# 4x4.net
KiCad netlist of a schematic drawn in Altium Designer
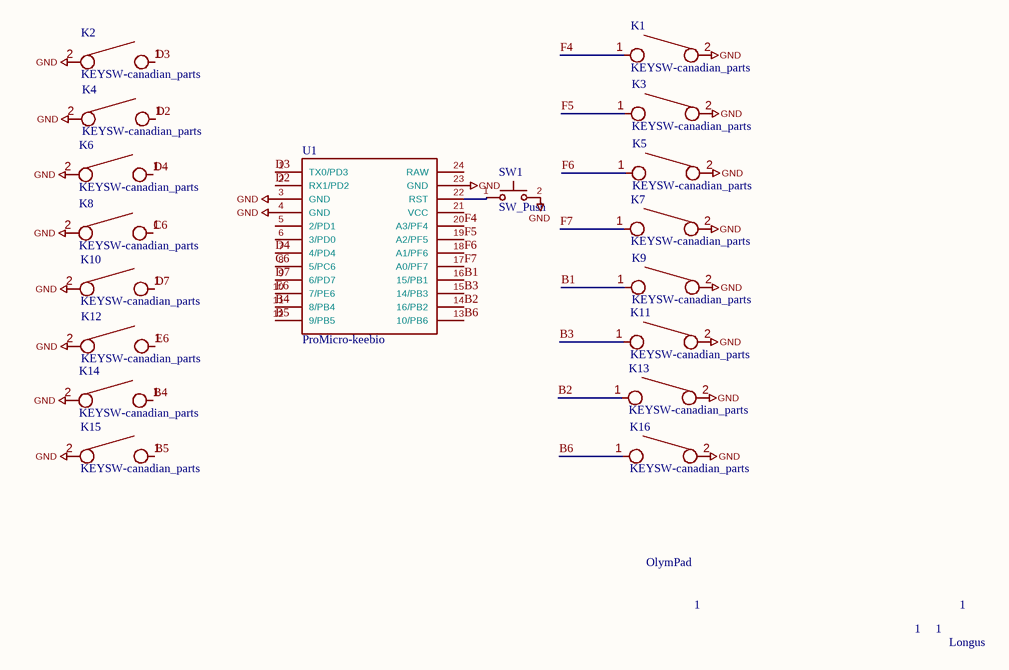
[diagram p0: 4x4.SchDoc]

(export (version "E")
  (design (tool "Eeschema 10.0.6"))
  (components
    (comp (ref "K1")
      (value "KEYSW-canadian_parts")
      (footprint "Socket")
      (libsource (lib "Macropad") (part "KEYSW-canadian_parts"))
    )
    (comp (ref "K2")
      (value "KEYSW-canadian_parts")
      (footprint "Socket")
      (libsource (lib "Macropad") (part "KEYSW-canadian_parts"))
    )
    (comp (ref "K3")
      (value "KEYSW-canadian_parts")
      (footprint "Socket")
      (libsource (lib "Macropad") (part "KEYSW-canadian_parts"))
    )
    (comp (ref "K4")
      (value "KEYSW-canadian_parts")
      (footprint "Socket")
      (libsource (lib "Macropad") (part "KEYSW-canadian_parts"))
    )
    (comp (ref "K5")
      (value "KEYSW-canadian_parts")
      (footprint "Socket")
      (libsource (lib "Macropad") (part "KEYSW-canadian_parts"))
    )
    (comp (ref "K6")
      (value "KEYSW-canadian_parts")
      (footprint "Socket")
      (libsource (lib "Macropad") (part "KEYSW-canadian_parts"))
    )
    (comp (ref "K7")
      (value "KEYSW-canadian_parts")
      (footprint "Socket")
      (libsource (lib "Macropad") (part "KEYSW-canadian_parts"))
    )
    (comp (ref "K8")
      (value "KEYSW-canadian_parts")
      (footprint "Socket")
      (libsource (lib "Macropad") (part "KEYSW-canadian_parts"))
    )
    (comp (ref "K9")
      (value "KEYSW-canadian_parts")
      (footprint "Socket")
      (libsource (lib "Macropad") (part "KEYSW-canadian_parts"))
    )
    (comp (ref "K10")
      (value "KEYSW-canadian_parts")
      (footprint "Socket")
      (libsource (lib "Macropad") (part "KEYSW-canadian_parts"))
    )
    (comp (ref "K11")
      (value "KEYSW-canadian_parts")
      (footprint "Socket")
      (libsource (lib "Macropad") (part "KEYSW-canadian_parts"))
    )
    (comp (ref "K12")
      (value "KEYSW-canadian_parts")
      (footprint "Socket")
      (libsource (lib "Macropad") (part "KEYSW-canadian_parts"))
    )
    (comp (ref "K13")
      (value "KEYSW-canadian_parts")
      (footprint "Socket")
      (libsource (lib "Macropad") (part "KEYSW-canadian_parts"))
    )
    (comp (ref "K14")
      (value "KEYSW-canadian_parts")
      (footprint "Socket")
      (libsource (lib "Macropad") (part "KEYSW-canadian_parts"))
    )
    (comp (ref "K15")
      (value "KEYSW-canadian_parts")
      (footprint "Socket")
      (libsource (lib "Macropad") (part "KEYSW-canadian_parts"))
    )
    (comp (ref "K16")
      (value "KEYSW-canadian_parts")
      (footprint "Socket")
      (libsource (lib "Macropad") (part "KEYSW-canadian_parts"))
    )
    (comp (ref "SW1") (value "SW_Push") (footprint "Reset") (libsource (lib "Macropad") (part "SW_Push")))
    (comp (ref "U1")
      (value "ProMicro-keebio")
      (footprint "Pro-Micro")
      (libsource (lib "Macropad") (part "ProMicro-keebio"))
    )
  )
  (nets
    (net (code "1") (name "/B1") (class "Default")
      (node (ref "K9") (pin "1") (pinfunction "1_1") (pintype "passive"))
      (node (ref "U1") (pin "16") (pinfunction "15/PB1_16") (pintype "passive"))
    )
    (net (code "2") (name "/B2") (class "Default")
      (node (ref "K13") (pin "1") (pinfunction "1_1") (pintype "passive"))
      (node (ref "U1") (pin "14") (pinfunction "16/PB2_14") (pintype "passive"))
    )
    (net (code "3") (name "/B3") (class "Default")
      (node (ref "K11") (pin "1") (pinfunction "1_1") (pintype "passive"))
      (node (ref "U1") (pin "15") (pinfunction "14/PB3_15") (pintype "passive"))
    )
    (net (code "4") (name "/B4") (class "Default")
      (node (ref "K14") (pin "1") (pinfunction "1_1") (pintype "passive"))
      (node (ref "U1") (pin "11") (pinfunction "8/PB4_11") (pintype "passive"))
    )
    (net (code "5") (name "/B5") (class "Default")
      (node (ref "K15") (pin "1") (pinfunction "1_1") (pintype "passive"))
      (node (ref "U1") (pin "12") (pinfunction "9/PB5_12") (pintype "passive"))
    )
    (net (code "6") (name "/B6") (class "Default")
      (node (ref "K16") (pin "1") (pinfunction "1_1") (pintype "passive"))
      (node (ref "U1") (pin "13") (pinfunction "10/PB6_13") (pintype "passive"))
    )
    (net (code "7") (name "/C6") (class "Default")
      (node (ref "K8") (pin "1") (pinfunction "1_1") (pintype "passive"))
      (node (ref "U1") (pin "8") (pinfunction "5/PC6_8") (pintype "passive"))
    )
    (net (code "8") (name "/D2") (class "Default")
      (node (ref "K4") (pin "1") (pinfunction "1_1") (pintype "passive"))
      (node (ref "U1") (pin "2") (pinfunction "RX1/PD2_2") (pintype "passive"))
    )
    (net (code "9") (name "/D3") (class "Default")
      (node (ref "K2") (pin "1") (pinfunction "1_1") (pintype "passive"))
      (node (ref "U1") (pin "1") (pinfunction "TX0/PD3_1") (pintype "passive"))
    )
    (net (code "10") (name "/D4") (class "Default")
      (node (ref "K6") (pin "1") (pinfunction "1_1") (pintype "passive"))
      (node (ref "U1") (pin "7") (pinfunction "4/PD4_7") (pintype "passive"))
    )
    (net (code "11") (name "/D7") (class "Default")
      (node (ref "K10") (pin "1") (pinfunction "1_1") (pintype "passive"))
      (node (ref "U1") (pin "9") (pinfunction "6/PD7_9") (pintype "passive"))
    )
    (net (code "12") (name "/E6") (class "Default")
      (node (ref "K12") (pin "1") (pinfunction "1_1") (pintype "passive"))
      (node (ref "U1") (pin "10") (pinfunction "7/PE6_10") (pintype "passive"))
    )
    (net (code "13") (name "/F4") (class "Default")
      (node (ref "K1") (pin "1") (pinfunction "1_1") (pintype "passive"))
      (node (ref "U1") (pin "20") (pinfunction "A3/PF4_20") (pintype "passive"))
    )
    (net (code "14") (name "/F5") (class "Default")
      (node (ref "K3") (pin "1") (pinfunction "1_1") (pintype "passive"))
      (node (ref "U1") (pin "19") (pinfunction "A2/PF5_19") (pintype "passive"))
    )
    (net (code "15") (name "/F6") (class "Default")
      (node (ref "K5") (pin "1") (pinfunction "1_1") (pintype "passive"))
      (node (ref "U1") (pin "18") (pinfunction "A1/PF6_18") (pintype "passive"))
    )
    (net (code "16") (name "/F7") (class "Default")
      (node (ref "K7") (pin "1") (pinfunction "1_1") (pintype "passive"))
      (node (ref "U1") (pin "17") (pinfunction "A0/PF7_17") (pintype "passive"))
    )
    (net (code "17") (name "GND") (class "Default")
      (node (ref "K1") (pin "2") (pinfunction "2_2") (pintype "passive"))
      (node (ref "K10") (pin "2") (pinfunction "2_2") (pintype "passive"))
      (node (ref "K11") (pin "2") (pinfunction "2_2") (pintype "passive"))
      (node (ref "K12") (pin "2") (pinfunction "2_2") (pintype "passive"))
      (node (ref "K13") (pin "2") (pinfunction "2_2") (pintype "passive"))
      (node (ref "K14") (pin "2") (pinfunction "2_2") (pintype "passive"))
      (node (ref "K15") (pin "2") (pinfunction "2_2") (pintype "passive"))
      (node (ref "K16") (pin "2") (pinfunction "2_2") (pintype "passive"))
      (node (ref "K2") (pin "2") (pinfunction "2_2") (pintype "passive"))
      (node (ref "K3") (pin "2") (pinfunction "2_2") (pintype "passive"))
      (node (ref "K4") (pin "2") (pinfunction "2_2") (pintype "passive"))
      (node (ref "K5") (pin "2") (pinfunction "2_2") (pintype "passive"))
      (node (ref "K6") (pin "2") (pinfunction "2_2") (pintype "passive"))
      (node (ref "K7") (pin "2") (pinfunction "2_2") (pintype "passive"))
      (node (ref "K8") (pin "2") (pinfunction "2_2") (pintype "passive"))
      (node (ref "K9") (pin "2") (pinfunction "2_2") (pintype "passive"))
      (node (ref "SW1") (pin "2") (pinfunction "2_2") (pintype "passive"))
      (node (ref "U1") (pin "23") (pinfunction "GND_23") (pintype "passive"))
      (node (ref "U1") (pin "3") (pinfunction "GND_3") (pintype "passive"))
      (node (ref "U1") (pin "4") (pinfunction "GND_4") (pintype "passive"))
    )
    (net (code "18") (name "Net-(U1-RST)") (class "Default")
      (node (ref "SW1") (pin "1") (pinfunction "1_1") (pintype "passive"))
      (node (ref "U1") (pin "22") (pinfunction "RST_22") (pintype "passive"))
    )
    (net (code "19") (name "unconnected-(U1-2{slash}PD1-Pad5)") (class "Default")
      (node (ref "U1") (pin "5") (pinfunction "2/PD1_5") (pintype "passive"))
    )
    (net (code "20") (name "unconnected-(U1-3{slash}PD0-Pad6)") (class "Default")
      (node (ref "U1") (pin "6") (pinfunction "3/PD0_6") (pintype "passive"))
    )
    (net (code "21") (name "unconnected-(U1-RAW-Pad24)") (class "Default")
      (node (ref "U1") (pin "24") (pinfunction "RAW_24") (pintype "passive"))
    )
    (net (code "22") (name "unconnected-(U1-VCC-Pad21)") (class "Default")
      (node (ref "U1") (pin "21") (pinfunction "VCC_21") (pintype "passive"))
    )
  )
)
